# PPSDriver.net
KiCad netlist of a schematic drawn in Altium Designer
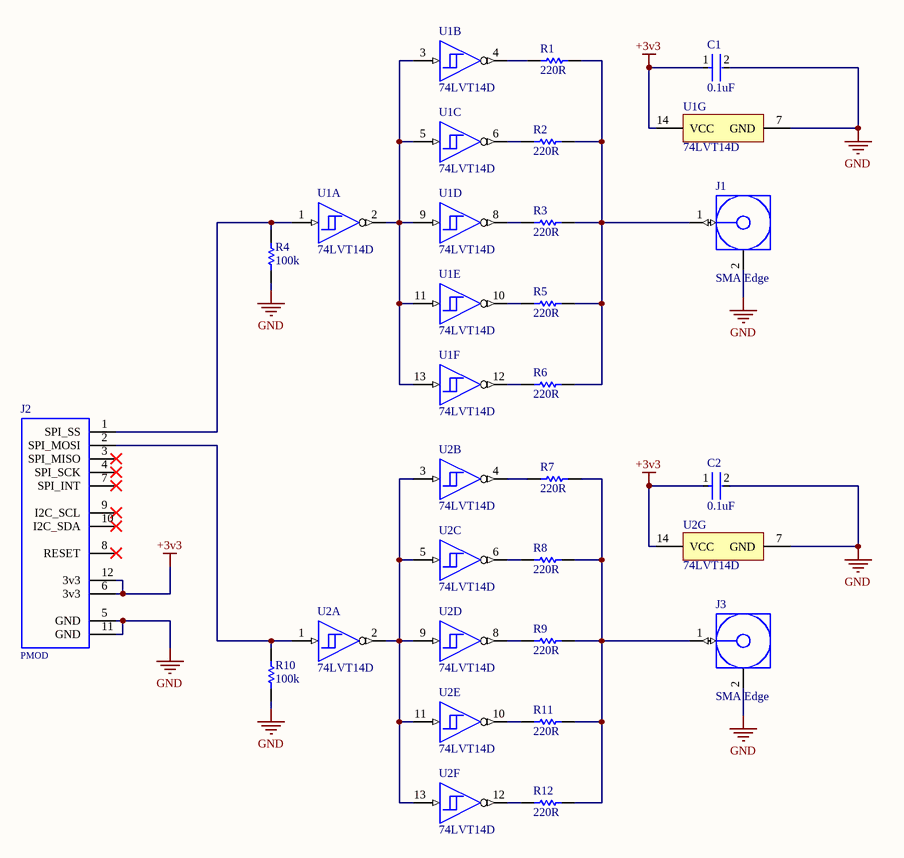
[diagram p0: PPSDriver.SchDoc]

(export (version "E")
  (design (tool "Eeschema 10.0.6"))
  (components
    (comp (ref "C1")
      (value "0.1uF")
      (footprint "FP-CC0603-DA-IPC_B")
      (description "CAP CER 0.1UF 16V X7R 0603")
      (fields
        (field (name "OCTOPART") "https://octopart.com/cc0603krx7r7bb104-yageo-192941")
        (field (name "TOLERANCE") "0.1")
      )
      (libsource (lib "LeafLabs_Commercial") (part "CAP-0603-0.1uF"))
    )
    (comp (ref "C2")
      (value "0.1uF")
      (footprint "FP-CC0603-DA-IPC_B")
      (description "CAP CER 0.1UF 16V X7R 0603")
      (fields
        (field (name "OCTOPART") "https://octopart.com/cc0603krx7r7bb104-yageo-192941")
        (field (name "TOLERANCE") "0.1")
      )
      (libsource (lib "LeafLabs_Commercial") (part "CAP-0603-0.1uF"))
    )
    (comp (ref "J1")
      (value "SMA Edge")
      (footprint "FP-CON-SMA-EDGE-S-MFG")
      (description "50 Ohm Edge mount SMA")
      (libsource (lib "Connectors") (part "SMA_EDGE"))
    )
    (comp (ref "J2")
      (value "PMOD")
      (footprint "PMOD")
      (description "PMOD Connector, Through Hole, Standard pinout")
      (fields (field (name "PUBLISHER") "WurthElektronik"))
      (libsource (lib "LeafLabs_Commercial") (part "PMOD-TH"))
    )
    (comp (ref "J3")
      (value "SMA Edge")
      (footprint "FP-CON-SMA-EDGE-S-MFG")
      (description "50 Ohm Edge mount SMA")
      (libsource (lib "Connectors") (part "SMA_EDGE"))
    )
    (comp (ref "R1")
      (value "220R")
      (footprint "RESC1609X50X30NL10T20")
      (description "Resistor 0603 220 Ohm")
      (libsource (lib "LeafLabs_Commercial") (part "RES-0603-220R"))
    )
    (comp (ref "R2")
      (value "220R")
      (footprint "RESC1609X50X30NL10T20")
      (description "Resistor 0603 220 Ohm")
      (libsource (lib "LeafLabs_Commercial") (part "RES-0603-220R"))
    )
    (comp (ref "R3")
      (value "220R")
      (footprint "RESC1609X50X30NL10T20")
      (description "Resistor 0603 220 Ohm")
      (libsource (lib "LeafLabs_Commercial") (part "RES-0603-220R"))
    )
    (comp (ref "R4")
      (value "100k")
      (footprint "RESC1609X50X30NL10T20")
      (description "Resistor 0603 100k Ohm")
      (libsource (lib "LeafLabs_Commercial") (part "RES-0603-100k"))
    )
    (comp (ref "R5")
      (value "220R")
      (footprint "RESC1609X50X30NL10T20")
      (description "Resistor 0603 220 Ohm")
      (libsource (lib "LeafLabs_Commercial") (part "RES-0603-220R"))
    )
    (comp (ref "R6")
      (value "220R")
      (footprint "RESC1609X50X30NL10T20")
      (description "Resistor 0603 220 Ohm")
      (libsource (lib "LeafLabs_Commercial") (part "RES-0603-220R"))
    )
    (comp (ref "R7")
      (value "220R")
      (footprint "RESC1609X50X30NL10T20")
      (description "Resistor 0603 220 Ohm")
      (libsource (lib "LeafLabs_Commercial") (part "RES-0603-220R"))
    )
    (comp (ref "R8")
      (value "220R")
      (footprint "RESC1609X50X30NL10T20")
      (description "Resistor 0603 220 Ohm")
      (libsource (lib "LeafLabs_Commercial") (part "RES-0603-220R"))
    )
    (comp (ref "R9")
      (value "220R")
      (footprint "RESC1609X50X30NL10T20")
      (description "Resistor 0603 220 Ohm")
      (libsource (lib "LeafLabs_Commercial") (part "RES-0603-220R"))
    )
    (comp (ref "R10")
      (value "100k")
      (footprint "RESC1609X50X30NL10T20")
      (description "Resistor 0603 100k Ohm")
      (libsource (lib "LeafLabs_Commercial") (part "RES-0603-100k"))
    )
    (comp (ref "R11")
      (value "220R")
      (footprint "RESC1609X50X30NL10T20")
      (description "Resistor 0603 220 Ohm")
      (libsource (lib "LeafLabs_Commercial") (part "RES-0603-220R"))
    )
    (comp (ref "R12")
      (value "220R")
      (footprint "RESC1609X50X30NL10T20")
      (description "Resistor 0603 220 Ohm")
      (libsource (lib "LeafLabs_Commercial") (part "RES-0603-220R"))
    )
    (comp (ref "U1")
      (value "74LVT14D")
      (footprint "SOIC14A_L")
      (description "Hex Schmitt-Trigger Inverters, D0014A, LARGE T&R")
      (fields (field (name "GENERIC PART NUMBER") "74LVT14"))
      (libsource (lib "LeafLabs_Commercial") (part "74LVT14D"))
    )
    (comp (ref "U2")
      (value "74LVT14D")
      (footprint "SOIC14A_L")
      (description "Hex Schmitt-Trigger Inverters, D0014A, LARGE T&R")
      (fields (field (name "GENERIC PART NUMBER") "74LVT14"))
      (libsource (lib "LeafLabs_Commercial") (part "74LVT14D"))
    )
  )
  (nets
    (net (code "1") (name "+3v3") (class "Default")
      (node (ref "C1") (pin "1") (pinfunction "1_1") (pintype "passive"))
      (node (ref "C2") (pin "1") (pinfunction "1_1") (pintype "passive"))
      (node (ref "J2") (pin "12") (pinfunction "3v3_12") (pintype "power_in"))
      (node (ref "J2") (pin "6") (pinfunction "3v3_6") (pintype "power_in"))
      (node (ref "U1") (pin "14") (pinfunction "VCC_14") (pintype "power_in"))
      (node (ref "U2") (pin "14") (pinfunction "VCC_14") (pintype "power_in"))
    )
    (net (code "2") (name "GND") (class "Default")
      (node (ref "C1") (pin "2") (pinfunction "2_2") (pintype "passive"))
      (node (ref "C2") (pin "2") (pinfunction "2_2") (pintype "passive"))
      (node (ref "J1") (pin "2") (pintype "power_in"))
      (node (ref "J2") (pin "11") (pinfunction "GND_11") (pintype "passive"))
      (node (ref "J2") (pin "5") (pinfunction "GND_5") (pintype "passive"))
      (node (ref "J3") (pin "2") (pintype "power_in"))
      (node (ref "R10") (pin "1") (pinfunction "1_1") (pintype "passive"))
      (node (ref "R4") (pin "1") (pinfunction "1_1") (pintype "passive"))
      (node (ref "U1") (pin "7") (pinfunction "GND_7") (pintype "power_in"))
      (node (ref "U2") (pin "7") (pinfunction "GND_7") (pintype "power_in"))
    )
    (net (code "3") (name "Net-(J1-Pad1)") (class "Default")
      (node (ref "J1") (pin "1") (pintype "bidirectional"))
      (node (ref "R1") (pin "2") (pinfunction "2_2") (pintype "passive"))
      (node (ref "R2") (pin "2") (pinfunction "2_2") (pintype "passive"))
      (node (ref "R3") (pin "2") (pinfunction "2_2") (pintype "passive"))
      (node (ref "R5") (pin "2") (pinfunction "2_2") (pintype "passive"))
      (node (ref "R6") (pin "2") (pinfunction "2_2") (pintype "passive"))
    )
    (net (code "4") (name "Net-(J2-SPI_MOSI)") (class "Default")
      (node (ref "J2") (pin "2") (pinfunction "SPI_MOSI_2") (pintype "passive"))
      (node (ref "R10") (pin "2") (pinfunction "2_2") (pintype "passive"))
      (node (ref "U2") (pin "1") (pinfunction "1A_1") (pintype "input"))
    )
    (net (code "5") (name "Net-(J2-SPI_SS)") (class "Default")
      (node (ref "J2") (pin "1") (pinfunction "SPI_SS_1") (pintype "passive"))
      (node (ref "R4") (pin "2") (pinfunction "2_2") (pintype "passive"))
      (node (ref "U1") (pin "1") (pinfunction "1A_1") (pintype "input"))
    )
    (net (code "6") (name "Net-(J3-Pad1)") (class "Default")
      (node (ref "J3") (pin "1") (pintype "bidirectional"))
      (node (ref "R11") (pin "2") (pinfunction "2_2") (pintype "passive"))
      (node (ref "R12") (pin "2") (pinfunction "2_2") (pintype "passive"))
      (node (ref "R7") (pin "2") (pinfunction "2_2") (pintype "passive"))
      (node (ref "R8") (pin "2") (pinfunction "2_2") (pintype "passive"))
      (node (ref "R9") (pin "2") (pinfunction "2_2") (pintype "passive"))
    )
    (net (code "7") (name "Net-(U1A-~{1Y})") (class "Default")
      (node (ref "U1") (pin "11") (pinfunction "5A_11") (pintype "input"))
      (node (ref "U1") (pin "13") (pinfunction "6A_13") (pintype "input"))
      (node (ref "U1") (pin "2") (pinfunction "~{1Y}_2") (pintype "output"))
      (node (ref "U1") (pin "3") (pinfunction "2A_3") (pintype "input"))
      (node (ref "U1") (pin "5") (pinfunction "3A_5") (pintype "input"))
      (node (ref "U1") (pin "9") (pinfunction "4A_9") (pintype "input"))
    )
    (net (code "8") (name "Net-(U1B-~{2Y})") (class "Default")
      (node (ref "R1") (pin "1") (pinfunction "1_1") (pintype "passive"))
      (node (ref "U1") (pin "4") (pinfunction "~{2Y}_4") (pintype "output"))
    )
    (net (code "9") (name "Net-(U1C-~{3Y})") (class "Default")
      (node (ref "R2") (pin "1") (pinfunction "1_1") (pintype "passive"))
      (node (ref "U1") (pin "6") (pinfunction "~{3Y}_6") (pintype "output"))
    )
    (net (code "10") (name "Net-(U1D-~{4Y})") (class "Default")
      (node (ref "R3") (pin "1") (pinfunction "1_1") (pintype "passive"))
      (node (ref "U1") (pin "8") (pinfunction "~{4Y}_8") (pintype "output"))
    )
    (net (code "11") (name "Net-(U1E-~{5Y})") (class "Default")
      (node (ref "R5") (pin "1") (pinfunction "1_1") (pintype "passive"))
      (node (ref "U1") (pin "10") (pinfunction "~{5Y}_10") (pintype "output"))
    )
    (net (code "12") (name "Net-(U1F-~{6Y})") (class "Default")
      (node (ref "R6") (pin "1") (pinfunction "1_1") (pintype "passive"))
      (node (ref "U1") (pin "12") (pinfunction "~{6Y}_12") (pintype "output"))
    )
    (net (code "13") (name "Net-(U2A-~{1Y})") (class "Default")
      (node (ref "U2") (pin "11") (pinfunction "5A_11") (pintype "input"))
      (node (ref "U2") (pin "13") (pinfunction "6A_13") (pintype "input"))
      (node (ref "U2") (pin "2") (pinfunction "~{1Y}_2") (pintype "output"))
      (node (ref "U2") (pin "3") (pinfunction "2A_3") (pintype "input"))
      (node (ref "U2") (pin "5") (pinfunction "3A_5") (pintype "input"))
      (node (ref "U2") (pin "9") (pinfunction "4A_9") (pintype "input"))
    )
    (net (code "14") (name "Net-(U2B-~{2Y})") (class "Default")
      (node (ref "R7") (pin "1") (pinfunction "1_1") (pintype "passive"))
      (node (ref "U2") (pin "4") (pinfunction "~{2Y}_4") (pintype "output"))
    )
    (net (code "15") (name "Net-(U2C-~{3Y})") (class "Default")
      (node (ref "R8") (pin "1") (pinfunction "1_1") (pintype "passive"))
      (node (ref "U2") (pin "6") (pinfunction "~{3Y}_6") (pintype "output"))
    )
    (net (code "16") (name "Net-(U2D-~{4Y})") (class "Default")
      (node (ref "R9") (pin "1") (pinfunction "1_1") (pintype "passive"))
      (node (ref "U2") (pin "8") (pinfunction "~{4Y}_8") (pintype "output"))
    )
    (net (code "17") (name "Net-(U2E-~{5Y})") (class "Default")
      (node (ref "R11") (pin "1") (pinfunction "1_1") (pintype "passive"))
      (node (ref "U2") (pin "10") (pinfunction "~{5Y}_10") (pintype "output"))
    )
    (net (code "18") (name "Net-(U2F-~{6Y})") (class "Default")
      (node (ref "R12") (pin "1") (pinfunction "1_1") (pintype "passive"))
      (node (ref "U2") (pin "12") (pinfunction "~{6Y}_12") (pintype "output"))
    )
    (net (code "19") (name "unconnected-(J2-I2C_SCL-Pad9)") (class "Default")
      (node (ref "J2") (pin "9") (pinfunction "I2C_SCL_9") (pintype "passive+no_connect"))
    )
    (net (code "20") (name "unconnected-(J2-I2C_SDA-Pad10)") (class "Default")
      (node (ref "J2") (pin "10") (pinfunction "I2C_SDA_10") (pintype "passive+no_connect"))
    )
    (net (code "21") (name "unconnected-(J2-RESET-Pad8)") (class "Default")
      (node (ref "J2") (pin "8") (pinfunction "RESET_8") (pintype "passive+no_connect"))
    )
    (net (code "22") (name "unconnected-(J2-SPI_INT-Pad7)") (class "Default")
      (node (ref "J2") (pin "7") (pinfunction "SPI_INT_7") (pintype "passive+no_connect"))
    )
    (net (code "23") (name "unconnected-(J2-SPI_MISO-Pad3)") (class "Default")
      (node (ref "J2") (pin "3") (pinfunction "SPI_MISO_3") (pintype "passive+no_connect"))
    )
    (net (code "24") (name "unconnected-(J2-SPI_SCK-Pad4)") (class "Default")
      (node (ref "J2") (pin "4") (pinfunction "SPI_SCK_4") (pintype "passive+no_connect"))
    )
  )
)
